# attiny85_0808_2016.net
KiCad netlist of a schematic drawn in EAGLE
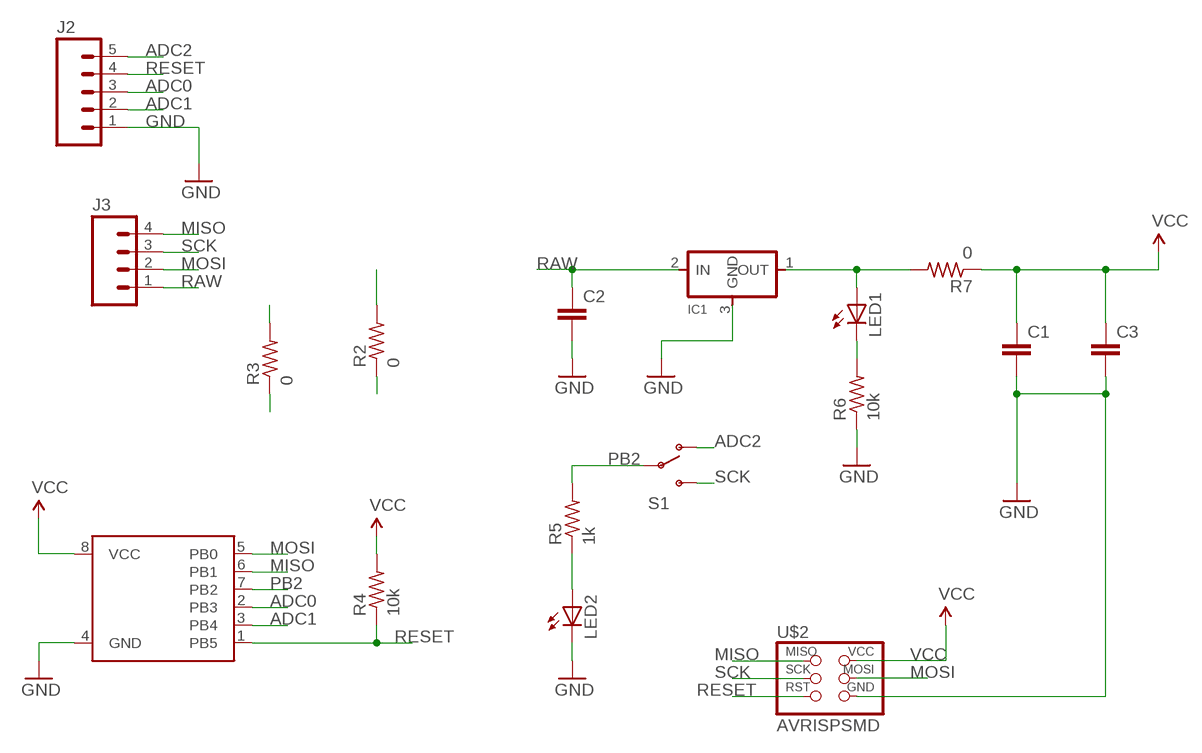
[diagram p0: schematic, sheet 1]

(export (version "E")
  (design (tool "Eeschema 10.0.6"))
  (components
    (comp (ref "C1")
      (value "CAP1206")
      (footprint "eagle-import:1206")
      (libsource (lib "eagle-import") (part "CAP1206"))
    )
    (comp (ref "C2")
      (value "CAP1206")
      (footprint "eagle-import:1206")
      (libsource (lib "eagle-import") (part "CAP1206"))
    )
    (comp (ref "C3")
      (value "CAP1206")
      (footprint "eagle-import:1206")
      (libsource (lib "eagle-import") (part "CAP1206"))
    )
    (comp (ref "IC1")
      (value "REGULATORSOT23")
      (footprint "eagle-import:SOT23")
      (libsource (lib "eagle-import") (part "REGULATORSOT23"))
    )
    (comp (ref "J2")
      (value "M05NO_SILK")
      (footprint "eagle-import:1X05_NO_SILK")
      (libsource (lib "eagle-import") (part "M05NO_SILK"))
    )
    (comp (ref "J3")
      (value "M04NO_SILK_ALL_ROUND")
      (footprint "eagle-import:1X04_NO_SILK_ALL_ROUND")
      (libsource (lib "eagle-import") (part "M04NO_SILK_ALL_ROUND"))
    )
    (comp (ref "LED1")
      (value "LEDCHIPLED_1206")
      (footprint "eagle-import:CHIPLED_1206")
      (libsource (lib "eagle-import") (part "LEDCHIPLED_1206"))
    )
    (comp (ref "LED2")
      (value "LEDCHIPLED_1206")
      (footprint "eagle-import:CHIPLED_1206")
      (libsource (lib "eagle-import") (part "LEDCHIPLED_1206"))
    )
    (comp (ref "R2")
      (value "0")
      (footprint "eagle-import:R1206FAB")
      (libsource (lib "eagle-import") (part "RES-US1206FAB"))
    )
    (comp (ref "R3")
      (value "0")
      (footprint "eagle-import:R1206FAB")
      (libsource (lib "eagle-import") (part "RES-US1206FAB"))
    )
    (comp (ref "R4")
      (value "10k")
      (footprint "eagle-import:R1206FAB")
      (libsource (lib "eagle-import") (part "RES-US1206FAB"))
    )
    (comp (ref "R5")
      (value "1k")
      (footprint "eagle-import:R1206FAB")
      (libsource (lib "eagle-import") (part "RES-US1206FAB"))
    )
    (comp (ref "R6")
      (value "10k")
      (footprint "eagle-import:R1206FAB")
      (libsource (lib "eagle-import") (part "RES-US1206FAB"))
    )
    (comp (ref "R7")
      (value "0")
      (footprint "eagle-import:R1206FAB")
      (libsource (lib "eagle-import") (part "RES-US1206FAB"))
    )
    (comp (ref "S1")
      (value "SWITCH-SPDTPTH")
      (footprint "eagle-import:SWITCH-SPDT")
      (libsource (lib "eagle-import") (part "SWITCH-SPDTPTH"))
    )
    (comp (ref "U$1")
      (value "ATTINY85EIAJ")
      (footprint "eagle-import:8S2_EIAJ-85")
      (libsource (lib "eagle-import") (part "ATTINY85EIAJ"))
    )
    (comp (ref "U$2")
      (value "AVRISPSMD")
      (footprint "eagle-import:2X03SMD")
      (libsource (lib "eagle-import") (part "AVRISPSMD"))
    )
  )
  (nets
    (net (code "1") (name "/ADC0") (class "Default")
      (node (ref "J2") (pin "3") (pinfunction "3_3") (pintype "passive"))
      (node (ref "U$1") (pin "2") (pinfunction "PB3_2") (pintype "bidirectional"))
    )
    (net (code "2") (name "/ADC1") (class "Default")
      (node (ref "J2") (pin "2") (pinfunction "2_2") (pintype "passive"))
      (node (ref "U$1") (pin "3") (pinfunction "PB4_3") (pintype "bidirectional"))
    )
    (net (code "3") (name "/ADC2") (class "Default")
      (node (ref "J2") (pin "5") (pinfunction "5_5") (pintype "passive"))
      (node (ref "S1") (pin "1") (pinfunction "O_1") (pintype "passive"))
    )
    (net (code "4") (name "/MISO") (class "Default")
      (node (ref "J3") (pin "4") (pinfunction "4_4") (pintype "passive"))
      (node (ref "U$1") (pin "6") (pinfunction "PB1_6") (pintype "bidirectional"))
      (node (ref "U$2") (pin "1") (pinfunction "MISO_1") (pintype "passive"))
    )
    (net (code "5") (name "/MOSI") (class "Default")
      (node (ref "J3") (pin "2") (pinfunction "2_2") (pintype "passive"))
      (node (ref "R2") (pin "1") (pinfunction "1_1") (pintype "passive"))
      (node (ref "R2") (pin "2") (pinfunction "2_2") (pintype "passive"))
      (node (ref "U$1") (pin "5") (pinfunction "PB0_5") (pintype "bidirectional"))
      (node (ref "U$2") (pin "4") (pinfunction "MOSI_4") (pintype "passive"))
    )
    (net (code "6") (name "/PB2") (class "Default")
      (node (ref "R5") (pin "2") (pinfunction "2_2") (pintype "passive"))
      (node (ref "S1") (pin "2") (pinfunction "P_2") (pintype "passive"))
      (node (ref "U$1") (pin "7") (pinfunction "PB2_7") (pintype "bidirectional"))
    )
    (net (code "7") (name "/RAW") (class "Default")
      (node (ref "C2") (pin "1") (pinfunction "1_1") (pintype "passive"))
      (node (ref "IC1") (pin "2") (pinfunction "IN_2") (pintype "bidirectional"))
      (node (ref "J3") (pin "1") (pinfunction "1_1") (pintype "passive"))
    )
    (net (code "8") (name "/RESET") (class "Default")
      (node (ref "J2") (pin "4") (pinfunction "4_4") (pintype "passive"))
      (node (ref "R4") (pin "1") (pinfunction "1_1") (pintype "passive"))
      (node (ref "U$1") (pin "1") (pinfunction "PB5_1") (pintype "bidirectional"))
      (node (ref "U$2") (pin "5") (pinfunction "RST_5") (pintype "passive"))
    )
    (net (code "9") (name "/SCK") (class "Default")
      (node (ref "J3") (pin "3") (pinfunction "3_3") (pintype "passive"))
      (node (ref "R3") (pin "1") (pinfunction "1_1") (pintype "passive"))
      (node (ref "R3") (pin "2") (pinfunction "2_2") (pintype "passive"))
      (node (ref "S1") (pin "3") (pinfunction "S_3") (pintype "passive"))
      (node (ref "U$2") (pin "3") (pinfunction "SCK_3") (pintype "passive"))
    )
    (net (code "10") (name "GND") (class "Default")
      (node (ref "C1") (pin "2") (pinfunction "2_2") (pintype "passive"))
      (node (ref "C2") (pin "2") (pinfunction "2_2") (pintype "passive"))
      (node (ref "C3") (pin "2") (pinfunction "2_2") (pintype "passive"))
      (node (ref "IC1") (pin "3") (pinfunction "GND_3") (pintype "bidirectional"))
      (node (ref "J2") (pin "1") (pinfunction "1_1") (pintype "passive"))
      (node (ref "LED2") (pin "C") (pinfunction "C_C") (pintype "passive"))
      (node (ref "R6") (pin "1") (pinfunction "1_1") (pintype "passive"))
      (node (ref "U$1") (pin "4") (pinfunction "GND_4") (pintype "power_in"))
      (node (ref "U$2") (pin "6") (pinfunction "GND_6") (pintype "passive"))
    )
    (net (code "11") (name "Net-(IC1-OUT)") (class "Default")
      (node (ref "IC1") (pin "1") (pinfunction "OUT_1") (pintype "bidirectional"))
      (node (ref "LED1") (pin "A") (pinfunction "A_A") (pintype "passive"))
      (node (ref "R7") (pin "2") (pinfunction "2_2") (pintype "passive"))
    )
    (net (code "12") (name "Net-(LED1-PadC)") (class "Default")
      (node (ref "LED1") (pin "C") (pinfunction "C_C") (pintype "passive"))
      (node (ref "R6") (pin "2") (pinfunction "2_2") (pintype "passive"))
    )
    (net (code "13") (name "Net-(LED2-PadA)") (class "Default")
      (node (ref "LED2") (pin "A") (pinfunction "A_A") (pintype "passive"))
      (node (ref "R5") (pin "1") (pinfunction "1_1") (pintype "passive"))
    )
    (net (code "14") (name "VCC") (class "Default")
      (node (ref "C1") (pin "1") (pinfunction "1_1") (pintype "passive"))
      (node (ref "C3") (pin "1") (pinfunction "1_1") (pintype "passive"))
      (node (ref "R4") (pin "2") (pinfunction "2_2") (pintype "passive"))
      (node (ref "R7") (pin "1") (pinfunction "1_1") (pintype "passive"))
      (node (ref "U$1") (pin "8") (pinfunction "VCC_8") (pintype "power_in"))
      (node (ref "U$2") (pin "2") (pinfunction "VCC_2") (pintype "passive"))
    )
  )
)
